# Current_Voltage_Dividers.net
KiCad netlist of a schematic drawn in Altium Designer
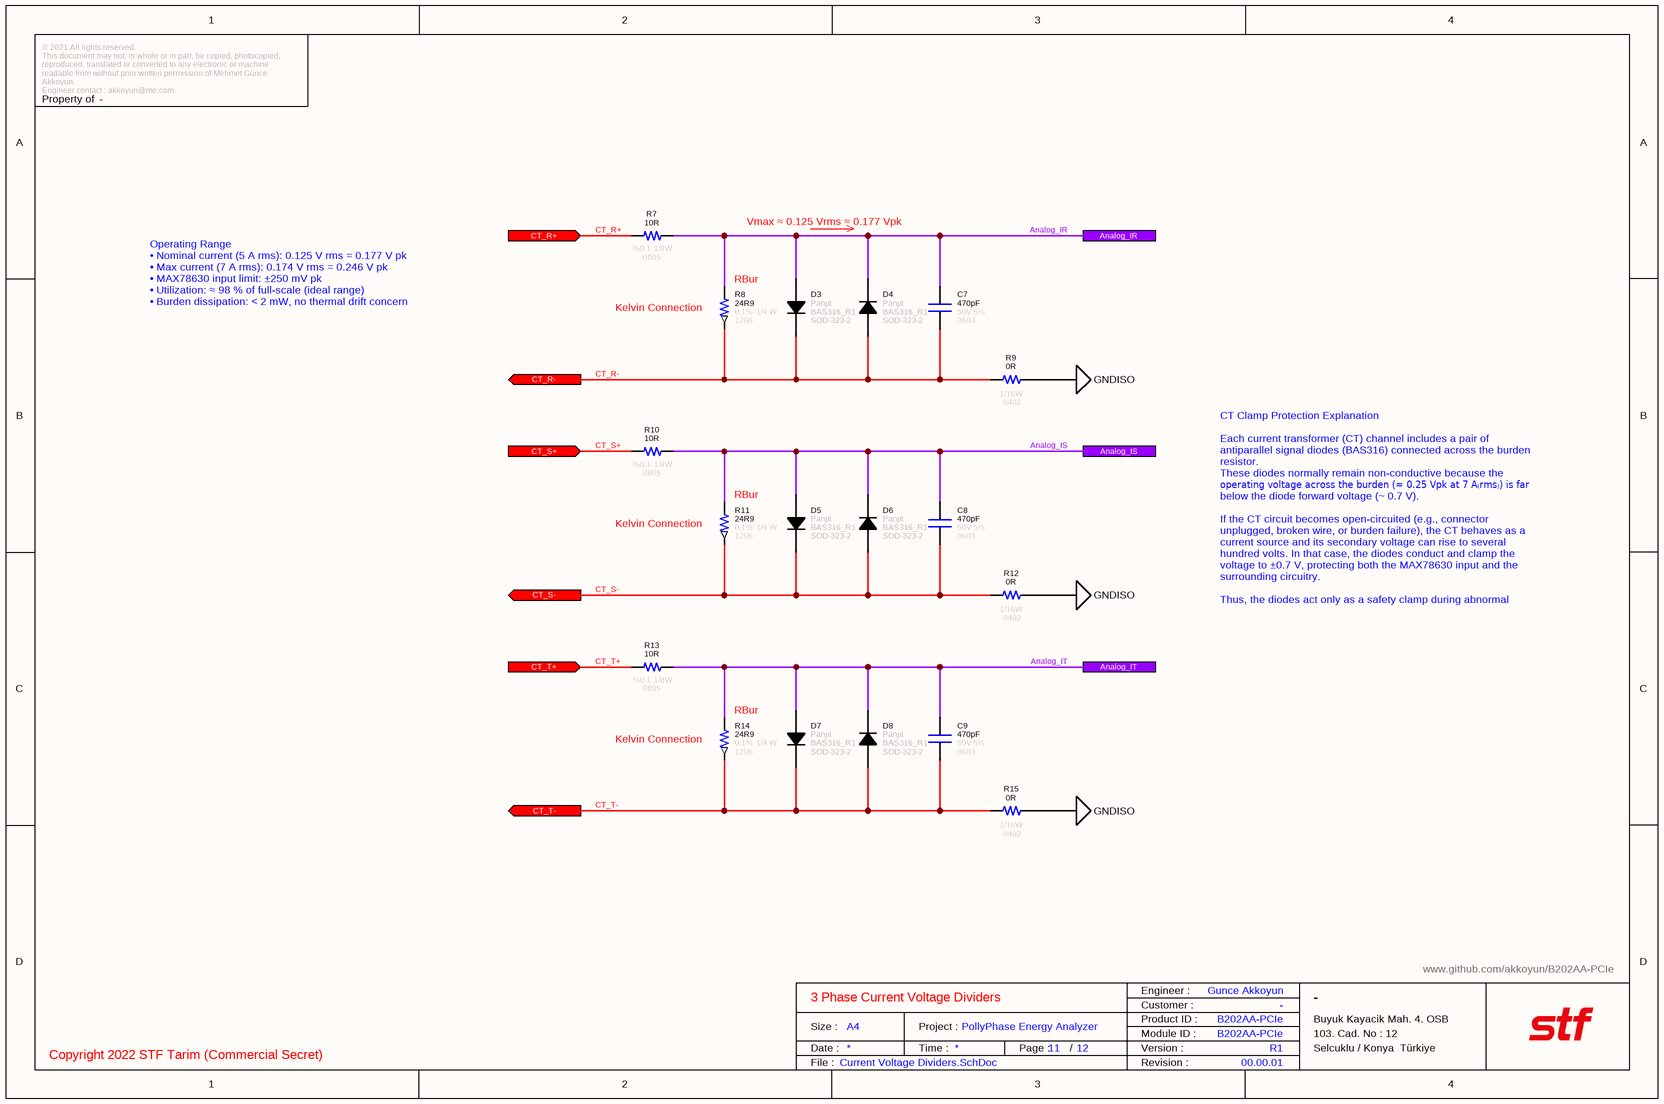
[diagram p0: Current Voltage Dividers.SchDoc]

(export (version "E")
  (design (tool "Eeschema 10.0.6"))
  (components
    (comp (ref "C7")
      (value "470pF")
      (footprint "CAPACITOR_0603")
      (description "Capacitor (MLCC) - 470pF / 50V / 0603")
      (fields
        (field (name "MANUFACTURER PART NUMBER") "GRM1885C1H471JA01")
        (field (name "TOLERANCE") "5%")
        (field (name "CASE") "0603")
        (field (name "VOLTAGE") "50V")
        (field (name "Comment") "Capacitor - 470pF [0603] (MLCC)")
      )
      (libsource (lib "Akkoyun") (part "Capacitor - 470 pF [0603-50V]"))
    )
    (comp (ref "C8")
      (value "470pF")
      (footprint "CAPACITOR_0603")
      (description "Capacitor (MLCC) - 470pF / 50V / 0603")
      (fields
        (field (name "MANUFACTURER PART NUMBER") "GRM1885C1H471JA01")
        (field (name "TOLERANCE") "5%")
        (field (name "CASE") "0603")
        (field (name "VOLTAGE") "50V")
        (field (name "Comment") "Capacitor - 470pF [0603] (MLCC)")
      )
      (libsource (lib "Akkoyun") (part "Capacitor - 470 pF [0603-50V]"))
    )
    (comp (ref "C9")
      (value "470pF")
      (footprint "CAPACITOR_0603")
      (description "Capacitor (MLCC) - 470pF / 50V / 0603")
      (fields
        (field (name "MANUFACTURER PART NUMBER") "GRM1885C1H471JA01")
        (field (name "TOLERANCE") "5%")
        (field (name "CASE") "0603")
        (field (name "VOLTAGE") "50V")
        (field (name "Comment") "Capacitor - 470pF [0603] (MLCC)")
      )
      (libsource (lib "Akkoyun") (part "Capacitor - 470 pF [0603-50V]"))
    )
    (comp (ref "D3")
      (value "BAS316_R1_00001")
      (footprint "SOD-323-2")
      (description "Small Signal Switching Diodes 100V,Small Signal Switching Diodes,SOD-323,4A")
      (fields
        (field (name "MANUFACTURER NAME") "Panjit")
        (field (name "MANUFACTURER PART NUMBER") "BAS316_R1")
        (field (name "CASE") "SOD-323-2")
      )
      (libsource (lib "Akkoyun") (part "Diode - BAS316_R1_00001"))
    )
    (comp (ref "D4")
      (value "BAS316_R1_00001")
      (footprint "SOD-323-2")
      (description "Small Signal Switching Diodes 100V,Small Signal Switching Diodes,SOD-323,4A")
      (fields
        (field (name "MANUFACTURER NAME") "Panjit")
        (field (name "MANUFACTURER PART NUMBER") "BAS316_R1")
        (field (name "CASE") "SOD-323-2")
      )
      (libsource (lib "Akkoyun") (part "Diode - BAS316_R1_00001"))
    )
    (comp (ref "D5")
      (value "BAS316_R1_00001")
      (footprint "SOD-323-2")
      (description "Small Signal Switching Diodes 100V,Small Signal Switching Diodes,SOD-323,4A")
      (fields
        (field (name "MANUFACTURER NAME") "Panjit")
        (field (name "MANUFACTURER PART NUMBER") "BAS316_R1")
        (field (name "CASE") "SOD-323-2")
      )
      (libsource (lib "Akkoyun") (part "Diode - BAS316_R1_00001"))
    )
    (comp (ref "D6")
      (value "BAS316_R1_00001")
      (footprint "SOD-323-2")
      (description "Small Signal Switching Diodes 100V,Small Signal Switching Diodes,SOD-323,4A")
      (fields
        (field (name "MANUFACTURER NAME") "Panjit")
        (field (name "MANUFACTURER PART NUMBER") "BAS316_R1")
        (field (name "CASE") "SOD-323-2")
      )
      (libsource (lib "Akkoyun") (part "Diode - BAS316_R1_00001"))
    )
    (comp (ref "D7")
      (value "BAS316_R1_00001")
      (footprint "SOD-323-2")
      (description "Small Signal Switching Diodes 100V,Small Signal Switching Diodes,SOD-323,4A")
      (fields
        (field (name "MANUFACTURER NAME") "Panjit")
        (field (name "MANUFACTURER PART NUMBER") "BAS316_R1")
        (field (name "CASE") "SOD-323-2")
      )
      (libsource (lib "Akkoyun") (part "Diode - BAS316_R1_00001"))
    )
    (comp (ref "D8")
      (value "BAS316_R1_00001")
      (footprint "SOD-323-2")
      (description "Small Signal Switching Diodes 100V,Small Signal Switching Diodes,SOD-323,4A")
      (fields
        (field (name "MANUFACTURER NAME") "Panjit")
        (field (name "MANUFACTURER PART NUMBER") "BAS316_R1")
        (field (name "CASE") "SOD-323-2")
      )
      (libsource (lib "Akkoyun") (part "Diode - BAS316_R1_00001"))
    )
    (comp (ref "R7")
      (value "10R")
      (footprint "RESISTOR_0805")
      (description "Thick Film Resistors - SMD 1/8 W 10 Ohm 0.1%")
      (fields
        (field (name "MANUFACTURER PART NUMBER") "RT0805BRD0710RL")
        (field (name "TOLERANCE") "%0.1")
        (field (name "CASE") "0805")
        (field (name "POWER") "1/8W")
        (field (name "Comment") "10R - 0805 - %0.1 - 1/8W")
      )
      (libsource (lib "Akkoyun") (part "Resistor - 10R [0805]"))
    )
    (comp (ref "R8")
      (value "24R9")
      (footprint "RESISTOR_1206")
      (description "Burden Resistors - SMD 1/4 W 24.9 Ohm 0.1%")
      (fields
        (field (name "MANUFACTURER PART NUMBER") "RT1206BRD0724R9L")
        (field (name "TOLERANCE") "0.1%")
        (field (name "POWER") "1/4 W")
        (field (name "CASE") "1206")
        (field (name "Comment") "24R9 - 1206 - %0.1 - 1/4W")
      )
      (libsource (lib "Akkoyun") (part "Resistor - 24R9 [1206]"))
    )
    (comp (ref "R9")
      (value "0R")
      (footprint "RESISTOR_0402")
      (description "Thick Film Resistors - SMD 1/16 W 0 Ohm")
      (fields
        (field (name "MANUFACTURER PART NUMBER") "CRCW04020000Z0ED")
        (field (name "CASE") "0402")
        (field (name "POWER") "1/16W")
        (field (name "Comment") "0R - 0402 - %1 - 1/16W")
      )
      (libsource (lib "Akkoyun") (part "Resistor - 0R [0402]"))
    )
    (comp (ref "R10")
      (value "10R")
      (footprint "RESISTOR_0805")
      (description "Thick Film Resistors - SMD 1/8 W 10 Ohm 0.1%")
      (fields
        (field (name "MANUFACTURER PART NUMBER") "RT0805BRD0710RL")
        (field (name "TOLERANCE") "%0.1")
        (field (name "CASE") "0805")
        (field (name "POWER") "1/8W")
        (field (name "Comment") "10R - 0805 - %0.1 - 1/8W")
      )
      (libsource (lib "Akkoyun") (part "Resistor - 10R [0805]"))
    )
    (comp (ref "R11")
      (value "24R9")
      (footprint "RESISTOR_1206")
      (description "Burden Resistors - SMD 1/4 W 24.9 Ohm 0.1%")
      (fields
        (field (name "MANUFACTURER PART NUMBER") "RT1206BRD0724R9L")
        (field (name "TOLERANCE") "0.1%")
        (field (name "POWER") "1/4 W")
        (field (name "CASE") "1206")
        (field (name "Comment") "24R9 - 1206 - %0.1 - 1/4W")
      )
      (libsource (lib "Akkoyun") (part "Resistor - 24R9 [1206]"))
    )
    (comp (ref "R12")
      (value "0R")
      (footprint "RESISTOR_0402")
      (description "Thick Film Resistors - SMD 1/16 W 0 Ohm")
      (fields
        (field (name "MANUFACTURER PART NUMBER") "CRCW04020000Z0ED")
        (field (name "CASE") "0402")
        (field (name "POWER") "1/16W")
        (field (name "Comment") "0R - 0402 - %1 - 1/16W")
      )
      (libsource (lib "Akkoyun") (part "Resistor - 0R [0402]"))
    )
    (comp (ref "R13")
      (value "10R")
      (footprint "RESISTOR_0805")
      (description "Thick Film Resistors - SMD 1/8 W 10 Ohm 0.1%")
      (fields
        (field (name "MANUFACTURER PART NUMBER") "RT0805BRD0710RL")
        (field (name "TOLERANCE") "%0.1")
        (field (name "CASE") "0805")
        (field (name "POWER") "1/8W")
        (field (name "Comment") "10R - 0805 - %0.1 - 1/8W")
      )
      (libsource (lib "Akkoyun") (part "Resistor - 10R [0805]"))
    )
    (comp (ref "R14")
      (value "24R9")
      (footprint "RESISTOR_1206")
      (description "Burden Resistors - SMD 1/4 W 24.9 Ohm 0.1%")
      (fields
        (field (name "MANUFACTURER PART NUMBER") "RT1206BRD0724R9L")
        (field (name "TOLERANCE") "0.1%")
        (field (name "POWER") "1/4 W")
        (field (name "CASE") "1206")
        (field (name "Comment") "24R9 - 1206 - %0.1 - 1/4W")
      )
      (libsource (lib "Akkoyun") (part "Resistor - 24R9 [1206]"))
    )
    (comp (ref "R15")
      (value "0R")
      (footprint "RESISTOR_0402")
      (description "Thick Film Resistors - SMD 1/16 W 0 Ohm")
      (fields
        (field (name "MANUFACTURER PART NUMBER") "CRCW04020000Z0ED")
        (field (name "CASE") "0402")
        (field (name "POWER") "1/16W")
        (field (name "Comment") "0R - 0402 - %1 - 1/16W")
      )
      (libsource (lib "Akkoyun") (part "Resistor - 0R [0402]"))
    )
  )
  (nets
    (net (code "1") (name "/Analog_IR") (class "Default")
      (node (ref "C7") (pin "2") (pinfunction "2_2") (pintype "passive"))
      (node (ref "D3") (pin "2") (pinfunction "Anode_2") (pintype "passive"))
      (node (ref "D4") (pin "1") (pinfunction "Cathode_1") (pintype "passive"))
      (node (ref "R7") (pin "1") (pinfunction "1_1") (pintype "passive"))
      (node (ref "R8") (pin "2") (pinfunction "2_2") (pintype "passive"))
    )
    (net (code "2") (name "/Analog_IS") (class "Default")
      (node (ref "C8") (pin "2") (pinfunction "2_2") (pintype "passive"))
      (node (ref "D5") (pin "2") (pinfunction "Anode_2") (pintype "passive"))
      (node (ref "D6") (pin "1") (pinfunction "Cathode_1") (pintype "passive"))
      (node (ref "R10") (pin "1") (pinfunction "1_1") (pintype "passive"))
      (node (ref "R11") (pin "2") (pinfunction "2_2") (pintype "passive"))
    )
    (net (code "3") (name "/Analog_IT") (class "Default")
      (node (ref "C9") (pin "2") (pinfunction "2_2") (pintype "passive"))
      (node (ref "D7") (pin "2") (pinfunction "Anode_2") (pintype "passive"))
      (node (ref "D8") (pin "1") (pinfunction "Cathode_1") (pintype "passive"))
      (node (ref "R13") (pin "1") (pinfunction "1_1") (pintype "passive"))
      (node (ref "R14") (pin "2") (pinfunction "2_2") (pintype "passive"))
    )
    (net (code "4") (name "/CT_R+") (class "Default")
      (node (ref "R7") (pin "2") (pinfunction "2_2") (pintype "passive"))
    )
    (net (code "5") (name "/CT_R-") (class "Default")
      (node (ref "C7") (pin "1") (pinfunction "1_1") (pintype "passive"))
      (node (ref "D3") (pin "1") (pinfunction "Cathode_1") (pintype "passive"))
      (node (ref "D4") (pin "2") (pinfunction "Anode_2") (pintype "passive"))
      (node (ref "R8") (pin "1") (pinfunction "1_1") (pintype "output"))
      (node (ref "R9") (pin "2") (pinfunction "2_2") (pintype "passive"))
    )
    (net (code "6") (name "/CT_S+") (class "Default")
      (node (ref "R10") (pin "2") (pinfunction "2_2") (pintype "passive"))
    )
    (net (code "7") (name "/CT_S-") (class "Default")
      (node (ref "C8") (pin "1") (pinfunction "1_1") (pintype "passive"))
      (node (ref "D5") (pin "1") (pinfunction "Cathode_1") (pintype "passive"))
      (node (ref "D6") (pin "2") (pinfunction "Anode_2") (pintype "passive"))
      (node (ref "R11") (pin "1") (pinfunction "1_1") (pintype "output"))
      (node (ref "R12") (pin "2") (pinfunction "2_2") (pintype "passive"))
    )
    (net (code "8") (name "/CT_T+") (class "Default")
      (node (ref "R13") (pin "2") (pinfunction "2_2") (pintype "passive"))
    )
    (net (code "9") (name "/CT_T-") (class "Default")
      (node (ref "C9") (pin "1") (pinfunction "1_1") (pintype "passive"))
      (node (ref "D7") (pin "1") (pinfunction "Cathode_1") (pintype "passive"))
      (node (ref "D8") (pin "2") (pinfunction "Anode_2") (pintype "passive"))
      (node (ref "R14") (pin "1") (pinfunction "1_1") (pintype "output"))
      (node (ref "R15") (pin "2") (pinfunction "2_2") (pintype "passive"))
    )
    (net (code "10") (name "GNDISO") (class "Default")
      (node (ref "R12") (pin "1") (pinfunction "1_1") (pintype "passive"))
      (node (ref "R15") (pin "1") (pinfunction "1_1") (pintype "passive"))
      (node (ref "R9") (pin "1") (pinfunction "1_1") (pintype "passive"))
    )
  )
)
